# schema_sensori_di_linea.net
KiCad netlist of a schematic drawn in EAGLE
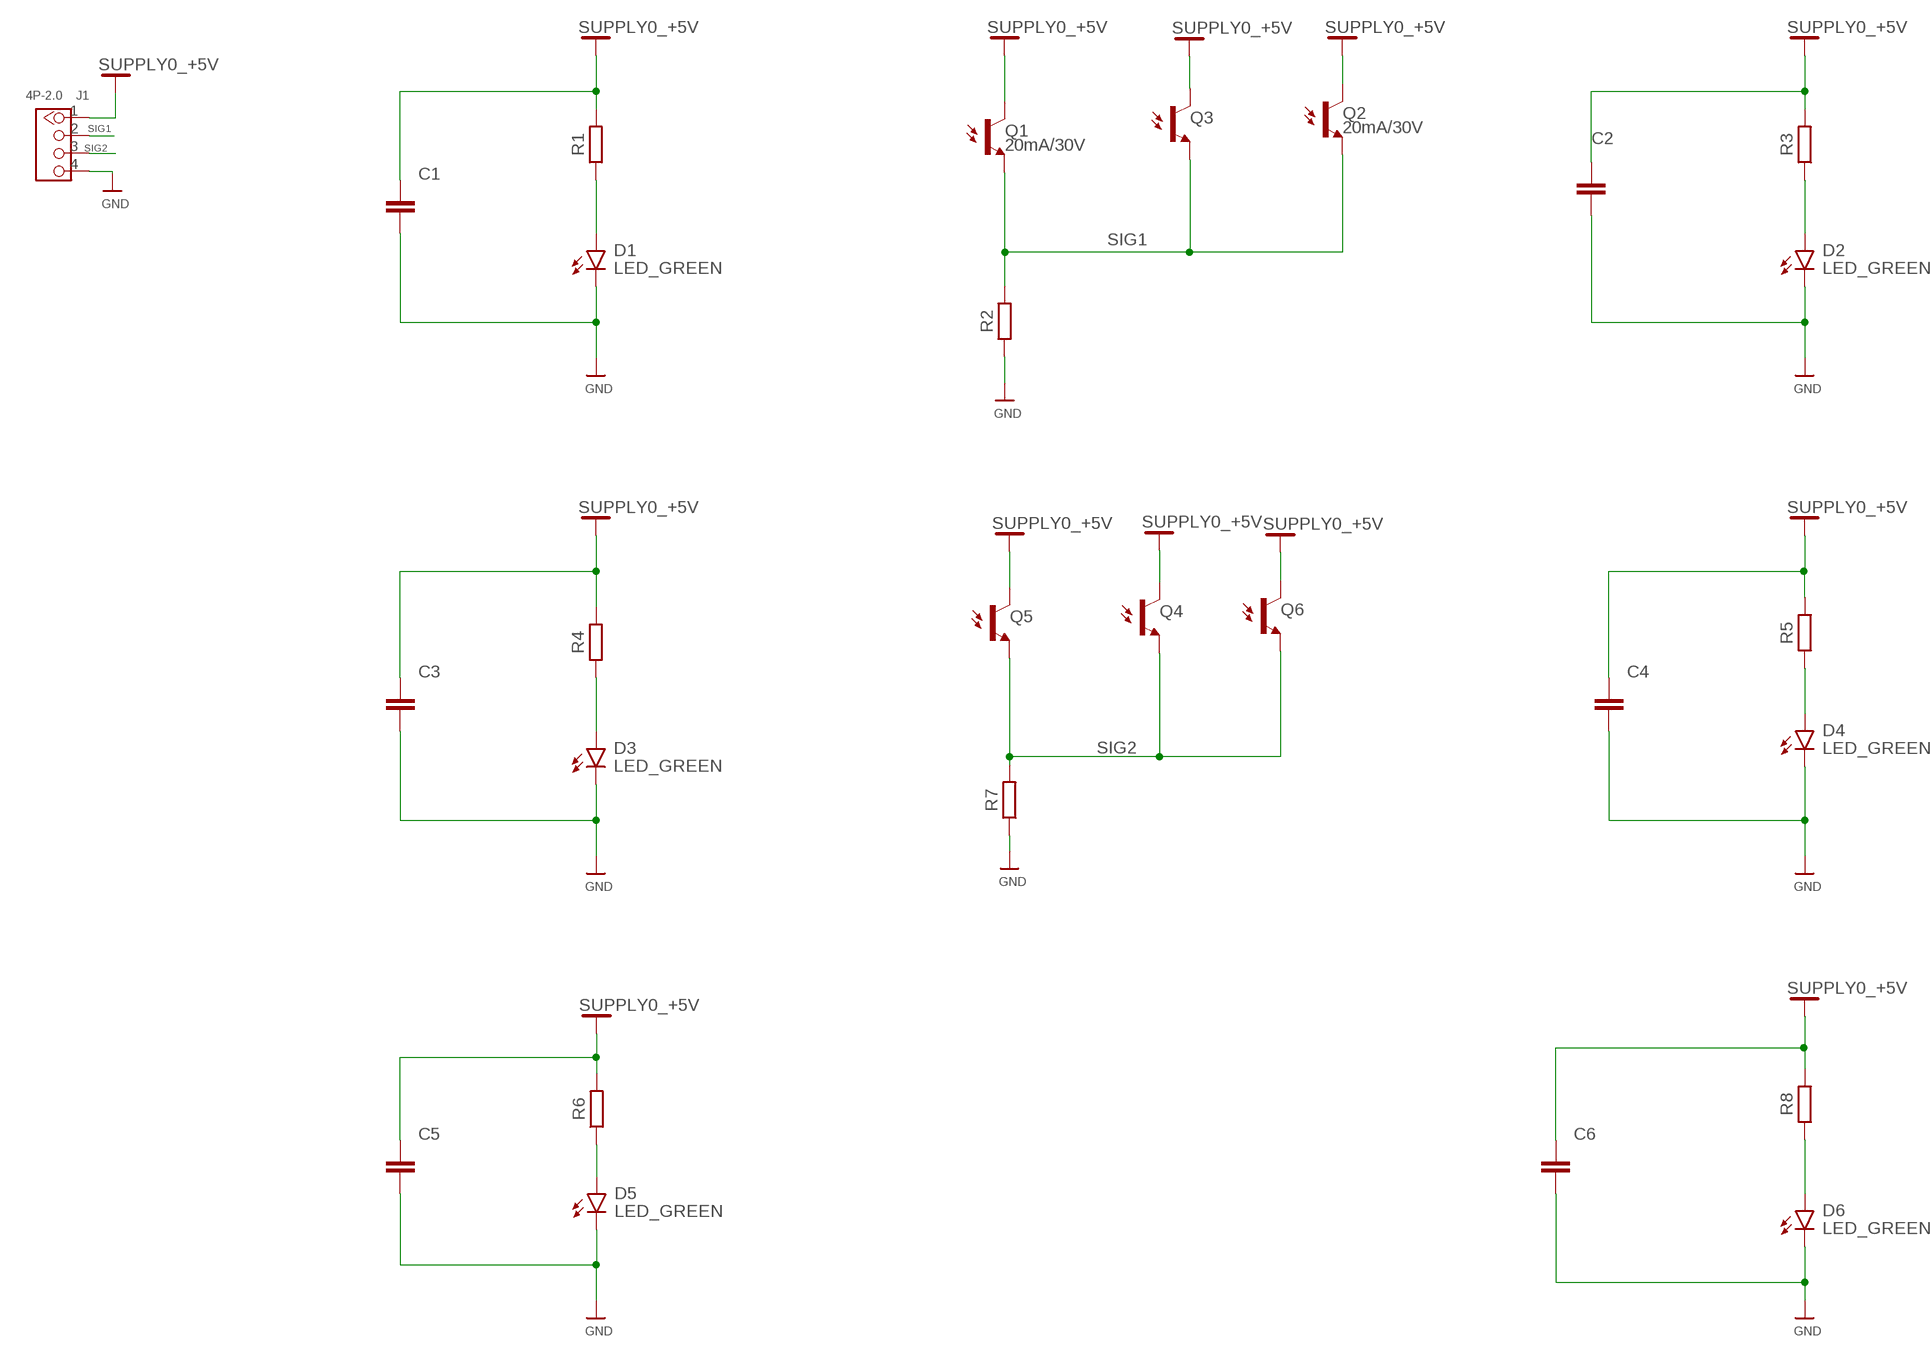
[diagram p0: schematic, sheet 1]

(export (version "E")
  (design (tool "Eeschema 10.0.6"))
  (components
    (comp (ref "C1")
      (value "100nf")
      (footprint "eagle-import:CAPC2012X110")
      (libsource (lib "eagle-import") (part "CCHIP-0805(2012-METRIC)_"))
    )
    (comp (ref "C2")
      (value "C_CHIP-0805(2012-METRIC)")
      (footprint "eagle-import:CAPC2012X110")
      (libsource (lib "eagle-import") (part "CCHIP-0805(2012-METRIC)_"))
    )
    (comp (ref "C3")
      (value "C_CHIP-0805(2012-METRIC)")
      (footprint "eagle-import:CAPC2012X110")
      (libsource (lib "eagle-import") (part "CCHIP-0805(2012-METRIC)_"))
    )
    (comp (ref "C4")
      (value "C_CHIP-0805(2012-METRIC)")
      (footprint "eagle-import:CAPC2012X110")
      (libsource (lib "eagle-import") (part "CCHIP-0805(2012-METRIC)_"))
    )
    (comp (ref "C5")
      (value "C_CHIP-0805(2012-METRIC)")
      (footprint "eagle-import:CAPC2012X110")
      (libsource (lib "eagle-import") (part "CCHIP-0805(2012-METRIC)_"))
    )
    (comp (ref "C6")
      (value "C_CHIP-0805(2012-METRIC)")
      (footprint "eagle-import:CAPC2012X110")
      (libsource (lib "eagle-import") (part "CCHIP-0805(2012-METRIC)_"))
    )
    (comp (ref "D1")
      (value "LED_GREEN")
      (footprint "eagle-import:LEDC2012X110N_FLAT-G")
      (libsource (lib "eagle-import") (part "CHIP-FLAT-G_0805"))
    )
    (comp (ref "D2")
      (value "LED_GREEN")
      (footprint "eagle-import:LEDC2012X110N_FLAT-G")
      (libsource (lib "eagle-import") (part "CHIP-FLAT-G_0805"))
    )
    (comp (ref "D3")
      (value "LED_GREEN")
      (footprint "eagle-import:LEDC2012X110N_FLAT-G")
      (libsource (lib "eagle-import") (part "CHIP-FLAT-G_0805"))
    )
    (comp (ref "D4")
      (value "LED_GREEN")
      (footprint "eagle-import:LEDC2012X110N_FLAT-G")
      (libsource (lib "eagle-import") (part "CHIP-FLAT-G_0805"))
    )
    (comp (ref "D5")
      (value "LED_GREEN")
      (footprint "eagle-import:LEDC2012X110N_FLAT-G")
      (libsource (lib "eagle-import") (part "CHIP-FLAT-G_0805"))
    )
    (comp (ref "D6")
      (value "LED_GREEN")
      (footprint "eagle-import:LEDC2012X110N_FLAT-G")
      (libsource (lib "eagle-import") (part "CHIP-FLAT-G_0805"))
    )
    (comp (ref "J1")
      (value "4P-2.0")
      (footprint "eagle-import:HW4-2.0")
      (libsource (lib "eagle-import") (part "GROVE-CONNECTOR-DIP(4P-2.0)"))
    )
    (comp (ref "Q1")
      (value "20mA/30V")
      (footprint "eagle-import:PT17-21C-L41-TR8")
      (libsource (lib "eagle-import") (part "PHOTOTRANSISTORPT17-21C-L41-TR8"))
    )
    (comp (ref "Q2")
      (value "20mA/30V")
      (footprint "eagle-import:PT17-21C-L41-TR8")
      (libsource (lib "eagle-import") (part "PHOTOTRANSISTORPT17-21C-L41-TR8"))
    )
    (comp (ref "Q3")
      (value "20mA/30V")
      (footprint "eagle-import:PT17-21C-L41-TR8")
      (libsource (lib "eagle-import") (part "PHOTOTRANSISTORPT17-21C-L41-TR8"))
    )
    (comp (ref "Q4")
      (value "20mA/30V")
      (footprint "eagle-import:PT17-21C-L41-TR8")
      (libsource (lib "eagle-import") (part "PHOTOTRANSISTORPT17-21C-L41-TR8"))
    )
    (comp (ref "Q5")
      (value "20mA/30V")
      (footprint "eagle-import:PT17-21C-L41-TR8")
      (libsource (lib "eagle-import") (part "PHOTOTRANSISTORPT17-21C-L41-TR8"))
    )
    (comp (ref "Q6")
      (value "20mA/30V")
      (footprint "eagle-import:PT17-21C-L41-TR8")
      (libsource (lib "eagle-import") (part "PHOTOTRANSISTORPT17-21C-L41-TR8"))
    )
    (comp (ref "R1")
      (value "330")
      (footprint "eagle-import:RESC2012X65")
      (libsource (lib "eagle-import") (part "RCHIP-0805(2012-METRIC)_"))
    )
    (comp (ref "R2")
      (value "R_CHIP-0805(2012-METRIC)")
      (footprint "eagle-import:RESC2012X65")
      (libsource (lib "eagle-import") (part "RCHIP-0805(2012-METRIC)_"))
    )
    (comp (ref "R3")
      (value "R_CHIP-0805(2012-METRIC)")
      (footprint "eagle-import:RESC2012X65")
      (libsource (lib "eagle-import") (part "RCHIP-0805(2012-METRIC)_"))
    )
    (comp (ref "R4")
      (value "R_CHIP-0805(2012-METRIC)")
      (footprint "eagle-import:RESC2012X65")
      (libsource (lib "eagle-import") (part "RCHIP-0805(2012-METRIC)_"))
    )
    (comp (ref "R5")
      (value "R_CHIP-0805(2012-METRIC)")
      (footprint "eagle-import:RESC2012X65")
      (libsource (lib "eagle-import") (part "RCHIP-0805(2012-METRIC)_"))
    )
    (comp (ref "R6")
      (value "R_CHIP-0805(2012-METRIC)")
      (footprint "eagle-import:RESC2012X65")
      (libsource (lib "eagle-import") (part "RCHIP-0805(2012-METRIC)_"))
    )
    (comp (ref "R7")
      (value "R_CHIP-0805(2012-METRIC)")
      (footprint "eagle-import:RESC2012X65")
      (libsource (lib "eagle-import") (part "RCHIP-0805(2012-METRIC)_"))
    )
    (comp (ref "R8")
      (value "R_CHIP-0805(2012-METRIC)")
      (footprint "eagle-import:RESC2012X65")
      (libsource (lib "eagle-import") (part "RCHIP-0805(2012-METRIC)_"))
    )
  )
  (nets
    (net (code "1") (name "/SIG1") (class "Default")
      (node (ref "J1") (pin "2") (pinfunction "2_2") (pintype "bidirectional"))
      (node (ref "Q1") (pin "E") (pinfunction "E_E") (pintype "passive"))
      (node (ref "Q2") (pin "E") (pinfunction "E_E") (pintype "passive"))
      (node (ref "Q3") (pin "E") (pinfunction "E_E") (pintype "passive"))
      (node (ref "R2") (pin "2") (pinfunction "2_2") (pintype "passive"))
    )
    (net (code "2") (name "/SIG2") (class "Default")
      (node (ref "J1") (pin "3") (pinfunction "3_3") (pintype "bidirectional"))
      (node (ref "Q4") (pin "E") (pinfunction "E_E") (pintype "passive"))
      (node (ref "Q5") (pin "E") (pinfunction "E_E") (pintype "passive"))
      (node (ref "Q6") (pin "E") (pinfunction "E_E") (pintype "passive"))
      (node (ref "R7") (pin "2") (pinfunction "2_2") (pintype "passive"))
    )
    (net (code "3") (name "GND") (class "Default")
      (node (ref "C1") (pin "2") (pinfunction "2_2") (pintype "passive"))
      (node (ref "C2") (pin "2") (pinfunction "2_2") (pintype "passive"))
      (node (ref "C3") (pin "2") (pinfunction "2_2") (pintype "passive"))
      (node (ref "C4") (pin "2") (pinfunction "2_2") (pintype "passive"))
      (node (ref "C5") (pin "2") (pinfunction "2_2") (pintype "passive"))
      (node (ref "C6") (pin "2") (pinfunction "2_2") (pintype "passive"))
      (node (ref "D1") (pin "C") (pinfunction "C_C") (pintype "passive"))
      (node (ref "D2") (pin "C") (pinfunction "C_C") (pintype "passive"))
      (node (ref "D3") (pin "C") (pinfunction "C_C") (pintype "passive"))
      (node (ref "D4") (pin "C") (pinfunction "C_C") (pintype "passive"))
      (node (ref "D5") (pin "C") (pinfunction "C_C") (pintype "passive"))
      (node (ref "D6") (pin "C") (pinfunction "C_C") (pintype "passive"))
      (node (ref "J1") (pin "4") (pinfunction "4_4") (pintype "bidirectional"))
      (node (ref "R2") (pin "1") (pinfunction "1_1") (pintype "passive"))
      (node (ref "R7") (pin "1") (pinfunction "1_1") (pintype "passive"))
    )
    (net (code "4") (name "Net-(D1-PadA)") (class "Default")
      (node (ref "D1") (pin "A") (pinfunction "A_A") (pintype "passive"))
      (node (ref "R1") (pin "1") (pinfunction "1_1") (pintype "passive"))
    )
    (net (code "5") (name "Net-(D2-PadA)") (class "Default")
      (node (ref "D2") (pin "A") (pinfunction "A_A") (pintype "passive"))
      (node (ref "R3") (pin "1") (pinfunction "1_1") (pintype "passive"))
    )
    (net (code "6") (name "Net-(D3-PadA)") (class "Default")
      (node (ref "D3") (pin "A") (pinfunction "A_A") (pintype "passive"))
      (node (ref "R4") (pin "1") (pinfunction "1_1") (pintype "passive"))
    )
    (net (code "7") (name "Net-(D4-PadA)") (class "Default")
      (node (ref "D4") (pin "A") (pinfunction "A_A") (pintype "passive"))
      (node (ref "R5") (pin "1") (pinfunction "1_1") (pintype "passive"))
    )
    (net (code "8") (name "Net-(D5-PadA)") (class "Default")
      (node (ref "D5") (pin "A") (pinfunction "A_A") (pintype "passive"))
      (node (ref "R6") (pin "1") (pinfunction "1_1") (pintype "passive"))
    )
    (net (code "9") (name "Net-(D6-PadA)") (class "Default")
      (node (ref "D6") (pin "A") (pinfunction "A_A") (pintype "passive"))
      (node (ref "R8") (pin "1") (pinfunction "1_1") (pintype "passive"))
    )
    (net (code "10") (name "SUPPLY0_+5V") (class "Default")
      (node (ref "C1") (pin "1") (pinfunction "1_1") (pintype "passive"))
      (node (ref "C2") (pin "1") (pinfunction "1_1") (pintype "passive"))
      (node (ref "C3") (pin "1") (pinfunction "1_1") (pintype "passive"))
      (node (ref "C4") (pin "1") (pinfunction "1_1") (pintype "passive"))
      (node (ref "C5") (pin "1") (pinfunction "1_1") (pintype "passive"))
      (node (ref "C6") (pin "1") (pinfunction "1_1") (pintype "passive"))
      (node (ref "J1") (pin "1") (pinfunction "1_1") (pintype "bidirectional"))
      (node (ref "Q1") (pin "C") (pinfunction "C_C") (pintype "passive"))
      (node (ref "Q2") (pin "C") (pinfunction "C_C") (pintype "passive"))
      (node (ref "Q3") (pin "C") (pinfunction "C_C") (pintype "passive"))
      (node (ref "Q4") (pin "C") (pinfunction "C_C") (pintype "passive"))
      (node (ref "Q5") (pin "C") (pinfunction "C_C") (pintype "passive"))
      (node (ref "Q6") (pin "C") (pinfunction "C_C") (pintype "passive"))
      (node (ref "R1") (pin "2") (pinfunction "2_2") (pintype "passive"))
      (node (ref "R3") (pin "2") (pinfunction "2_2") (pintype "passive"))
      (node (ref "R4") (pin "2") (pinfunction "2_2") (pintype "passive"))
      (node (ref "R5") (pin "2") (pinfunction "2_2") (pintype "passive"))
      (node (ref "R6") (pin "2") (pinfunction "2_2") (pintype "passive"))
      (node (ref "R8") (pin "2") (pinfunction "2_2") (pintype "passive"))
    )
  )
)
